# DS3231.net
KiCad netlist of a schematic drawn in Altium Designer
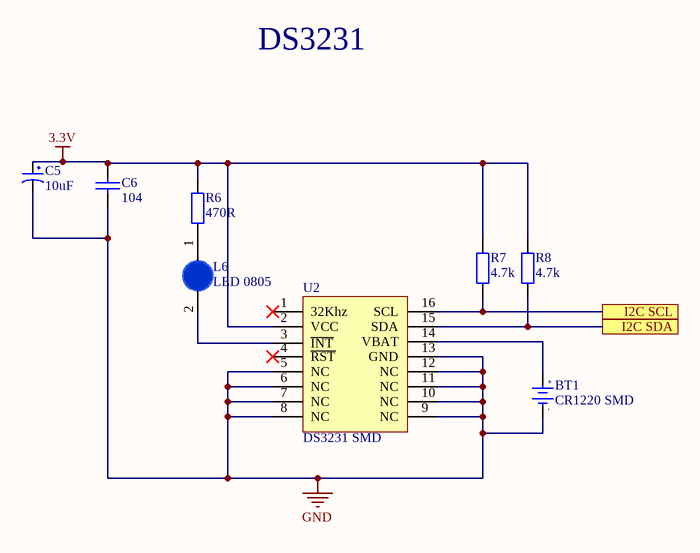
[diagram p0: DS3231.SchDoc]

(export (version "E")
  (design (tool "Eeschema 10.0.6"))
  (components
    (comp (ref "BT1")
      (value "CR1220 SMD")
      (footprint "DE PIN CR1220")
      (libsource (lib "Altium_Lib_by_KhueNguyenCreator") (part "De pin CR1220 SMD"))
    )
    (comp (ref "C5")
      (value "10uF")
      (footprint "tu tantalum smd3216")
      (description "Dán")
      (libsource (lib "Altium_Lib_by_KhueNguyenCreator") (part "Tu tantalum 10uF 16V SMD3216"))
    )
    (comp (ref "C6")
      (value "104")
      (footprint "tu 0805")
      (description "Dán")
      (libsource (lib "Altium_Lib_by_KhueNguyenCreator") (part "Tu 0805 104 50V 10%"))
    )
    (comp (ref "L6")
      (value "LED 0805")
      (footprint "LED-0805-Blue")
      (description "Dán")
      (libsource (lib "Altium_Lib_by_KhueNguyenCreator") (part "LED 0805 Xanh Duong"))
    )
    (comp (ref "R6")
      (value "470R")
      (footprint "Tro SMD 0805")
      (description "Dán")
      (libsource (lib "Altium_Lib_by_KhueNguyenCreator") (part "Tro 0805 5% 470R"))
    )
    (comp (ref "R7")
      (value "4.7k")
      (footprint "tro smd 0805")
      (description "Dán")
      (libsource (lib "Altium_Lib_by_KhueNguyenCreator") (part "Tro 0805 5% 4.7k"))
    )
    (comp (ref "R8")
      (value "4.7k")
      (footprint "tro smd 0805")
      (description "Dán")
      (libsource (lib "Altium_Lib_by_KhueNguyenCreator") (part "Tro 0805 5% 4.7k"))
    )
    (comp (ref "U2")
      (value "DS3231 SMD")
      (footprint "SOIC 16")
      (description "SOIC")
      (libsource (lib "Altium_Lib_by_KhueNguyenCreator") (part "DS3231 SMD"))
    )
  )
  (nets
    (net (code "1") (name "/I2C SCL") (class "Default")
      (node (ref "R7") (pin "1") (pinfunction "1_1") (pintype "passive"))
      (node (ref "U2") (pin "16") (pinfunction "SCL_16") (pintype "power_in"))
    )
    (net (code "2") (name "/I2C SDA") (class "Default")
      (node (ref "R8") (pin "1") (pinfunction "1_1") (pintype "passive"))
      (node (ref "U2") (pin "15") (pinfunction "SDA_15") (pintype "power_in"))
    )
    (net (code "3") (name "3.3V") (class "Default")
      (node (ref "C5") (pin "1") (pinfunction "1_1") (pintype "passive"))
      (node (ref "C6") (pin "1") (pinfunction "1_1") (pintype "passive"))
      (node (ref "R6") (pin "2") (pinfunction "2_2") (pintype "passive"))
      (node (ref "R7") (pin "2") (pinfunction "2_2") (pintype "passive"))
      (node (ref "R8") (pin "2") (pinfunction "2_2") (pintype "passive"))
      (node (ref "U2") (pin "2") (pinfunction "VCC_2") (pintype "power_in"))
    )
    (net (code "4") (name "GND") (class "Default")
      (node (ref "BT1") (pin "2") (pinfunction "GND_2") (pintype "passive"))
      (node (ref "C5") (pin "2") (pinfunction "2_2") (pintype "passive"))
      (node (ref "C6") (pin "2") (pinfunction "2_2") (pintype "passive"))
      (node (ref "U2") (pin "10") (pinfunction "NC_10") (pintype "power_in"))
      (node (ref "U2") (pin "11") (pinfunction "NC_11") (pintype "power_in"))
      (node (ref "U2") (pin "12") (pinfunction "NC_12") (pintype "power_in"))
      (node (ref "U2") (pin "13") (pinfunction "GND_13") (pintype "power_in"))
      (node (ref "U2") (pin "5") (pinfunction "NC_5") (pintype "power_in"))
      (node (ref "U2") (pin "6") (pinfunction "NC_6") (pintype "power_in"))
      (node (ref "U2") (pin "7") (pinfunction "NC_7") (pintype "power_in"))
      (node (ref "U2") (pin "8") (pinfunction "NC_8") (pintype "power_in"))
      (node (ref "U2") (pin "9") (pinfunction "NC_9") (pintype "power_in"))
    )
    (net (code "5") (name "Net-(BT1-+3V)") (class "Default")
      (node (ref "BT1") (pin "1") (pinfunction "+3V_1") (pintype "passive"))
      (node (ref "U2") (pin "14") (pinfunction "VBAT_14") (pintype "power_in"))
    )
    (net (code "6") (name "Net-(L6-A)") (class "Default")
      (node (ref "L6") (pin "1") (pinfunction "A_1") (pintype "passive"))
      (node (ref "R6") (pin "1") (pinfunction "1_1") (pintype "passive"))
    )
    (net (code "7") (name "Net-(L6-K)") (class "Default")
      (node (ref "L6") (pin "2") (pinfunction "K_2") (pintype "passive"))
      (node (ref "U2") (pin "3") (pinfunction "~{INT}_3") (pintype "power_in"))
    )
    (net (code "8") (name "unconnected-(U2-32Khz-Pad1)") (class "Default")
      (node (ref "U2") (pin "1") (pinfunction "32Khz_1") (pintype "power_in+no_connect"))
    )
    (net (code "9") (name "unconnected-(U2-~{RST}-Pad4)") (class "Default")
      (node (ref "U2") (pin "4") (pinfunction "~{RST}_4") (pintype "power_in+no_connect"))
    )
  )
)
